# ICTester_v1.net
KiCad netlist of a schematic drawn in EAGLE
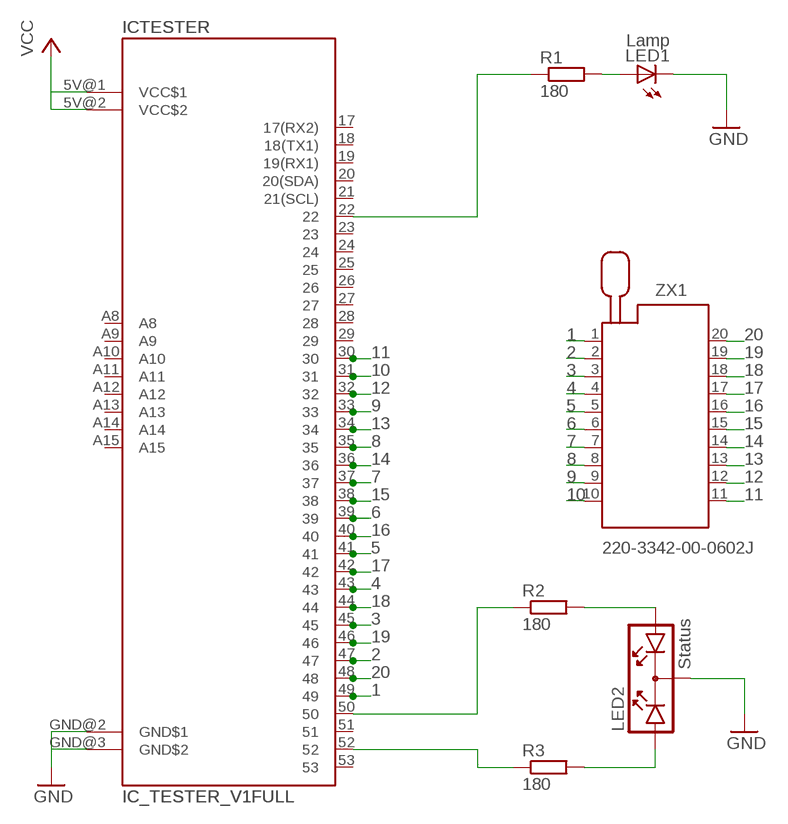
[diagram p0: schematic, sheet 1]

(export (version "E")
  (design (tool "Eeschema 10.0.6"))
  (components
    (comp (ref "ICTESTER")
      (value "IC_TESTER_V1FULL")
      (footprint "eagle-import:SPARKFUN-BOARDS_ARDUINO_MEGA")
      (libsource (lib "eagle-import") (part "IC_TESTER_V1FULL"))
    )
    (comp (ref "LED1")
      (value "Lamp")
      (footprint "eagle-import:LED3MM")
      (libsource (lib "eagle-import") (part "LED3MM"))
    )
    (comp (ref "LED2")
      (value "Status")
      (footprint "eagle-import:DUOLED")
      (libsource (lib "eagle-import") (part "DUOLED"))
    )
    (comp (ref "R1")
      (value "180")
      (footprint "eagle-import:0204V")
      (libsource (lib "eagle-import") (part "R-EU_0204/2V"))
    )
    (comp (ref "R2")
      (value "180")
      (footprint "eagle-import:0204_7")
      (libsource (lib "eagle-import") (part "R-EU_0204/7"))
    )
    (comp (ref "R3")
      (value "180")
      (footprint "eagle-import:0204_7")
      (libsource (lib "eagle-import") (part "R-EU_0204/7"))
    )
    (comp (ref "ZX1")
      (value "220-3342-00-0602J")
      (footprint "eagle-import:220-3342-00-0602J")
      (fields (field (name "MF") "3M"))
      (libsource (lib "eagle-import") (part "220-3342-00-0602J"))
    )
  )
  (nets
    (net (code "1") (name "/1") (class "Default")
      (node (ref "ICTESTER") (pin "49") (pinfunction "49_49") (pintype "bidirectional"))
      (node (ref "ZX1") (pin "1") (pinfunction "1_1") (pintype "passive"))
    )
    (net (code "2") (name "/2") (class "Default")
      (node (ref "ICTESTER") (pin "47") (pinfunction "47_47") (pintype "bidirectional"))
      (node (ref "ZX1") (pin "2") (pinfunction "2_2") (pintype "passive"))
    )
    (net (code "3") (name "/3") (class "Default")
      (node (ref "ICTESTER") (pin "45") (pinfunction "45_45") (pintype "bidirectional"))
      (node (ref "ZX1") (pin "3") (pinfunction "3_3") (pintype "passive"))
    )
    (net (code "4") (name "/4") (class "Default")
      (node (ref "ICTESTER") (pin "43") (pinfunction "43_43") (pintype "bidirectional"))
      (node (ref "ZX1") (pin "4") (pinfunction "4_4") (pintype "passive"))
    )
    (net (code "5") (name "/5") (class "Default")
      (node (ref "ICTESTER") (pin "41") (pinfunction "41_41") (pintype "bidirectional"))
      (node (ref "ZX1") (pin "5") (pinfunction "5_5") (pintype "passive"))
    )
    (net (code "6") (name "/6") (class "Default")
      (node (ref "ICTESTER") (pin "39") (pinfunction "39_39") (pintype "bidirectional"))
      (node (ref "ZX1") (pin "6") (pinfunction "6_6") (pintype "passive"))
    )
    (net (code "7") (name "/7") (class "Default")
      (node (ref "ICTESTER") (pin "37") (pinfunction "37_37") (pintype "bidirectional"))
      (node (ref "ZX1") (pin "7") (pinfunction "7_7") (pintype "passive"))
    )
    (net (code "8") (name "/8") (class "Default")
      (node (ref "ICTESTER") (pin "35") (pinfunction "35_35") (pintype "bidirectional"))
      (node (ref "ZX1") (pin "8") (pinfunction "8_8") (pintype "passive"))
    )
    (net (code "9") (name "/9") (class "Default")
      (node (ref "ICTESTER") (pin "33") (pinfunction "33_33") (pintype "bidirectional"))
      (node (ref "ZX1") (pin "9") (pinfunction "9_9") (pintype "passive"))
    )
    (net (code "10") (name "/10") (class "Default")
      (node (ref "ICTESTER") (pin "31") (pinfunction "31_31") (pintype "bidirectional"))
      (node (ref "ZX1") (pin "10") (pinfunction "10_10") (pintype "passive"))
    )
    (net (code "11") (name "/11") (class "Default")
      (node (ref "ICTESTER") (pin "30") (pinfunction "30_30") (pintype "bidirectional"))
      (node (ref "ZX1") (pin "11") (pinfunction "11_11") (pintype "passive"))
    )
    (net (code "12") (name "/12") (class "Default")
      (node (ref "ICTESTER") (pin "32") (pinfunction "32_32") (pintype "bidirectional"))
      (node (ref "ZX1") (pin "12") (pinfunction "12_12") (pintype "passive"))
    )
    (net (code "13") (name "/13") (class "Default")
      (node (ref "ICTESTER") (pin "34") (pinfunction "34_34") (pintype "bidirectional"))
      (node (ref "ZX1") (pin "13") (pinfunction "13_13") (pintype "passive"))
    )
    (net (code "14") (name "/14") (class "Default")
      (node (ref "ICTESTER") (pin "36") (pinfunction "36_36") (pintype "bidirectional"))
      (node (ref "ZX1") (pin "14") (pinfunction "14_14") (pintype "passive"))
    )
    (net (code "15") (name "/15") (class "Default")
      (node (ref "ICTESTER") (pin "38") (pinfunction "38_38") (pintype "bidirectional"))
      (node (ref "ZX1") (pin "15") (pinfunction "15_15") (pintype "passive"))
    )
    (net (code "16") (name "/16") (class "Default")
      (node (ref "ICTESTER") (pin "40") (pinfunction "40_40") (pintype "bidirectional"))
      (node (ref "ZX1") (pin "16") (pinfunction "16_16") (pintype "passive"))
    )
    (net (code "17") (name "/17") (class "Default")
      (node (ref "ICTESTER") (pin "42") (pinfunction "42_42") (pintype "bidirectional"))
      (node (ref "ZX1") (pin "17") (pinfunction "17_17") (pintype "passive"))
    )
    (net (code "18") (name "/18") (class "Default")
      (node (ref "ICTESTER") (pin "44") (pinfunction "44_44") (pintype "bidirectional"))
      (node (ref "ZX1") (pin "18") (pinfunction "18_18") (pintype "passive"))
    )
    (net (code "19") (name "/19") (class "Default")
      (node (ref "ICTESTER") (pin "46") (pinfunction "46_46") (pintype "bidirectional"))
      (node (ref "ZX1") (pin "19") (pinfunction "19_19") (pintype "passive"))
    )
    (net (code "20") (name "/20") (class "Default")
      (node (ref "ICTESTER") (pin "48") (pinfunction "48_48") (pintype "bidirectional"))
      (node (ref "ZX1") (pin "20") (pinfunction "20_20") (pintype "passive"))
    )
    (net (code "21") (name "GND") (class "Default")
      (node (ref "ICTESTER") (pin "GND@2") (pinfunction "GND$1_GND@2") (pintype "power_in"))
      (node (ref "ICTESTER") (pin "GND@3") (pinfunction "GND$2_GND@3") (pintype "power_in"))
      (node (ref "LED1") (pin "K") (pinfunction "C_K") (pintype "passive"))
      (node (ref "LED2") (pin "K") (pinfunction "K_K") (pintype "passive"))
    )
    (net (code "22") (name "Net-(ICTESTER-Pad22)") (class "Default")
      (node (ref "ICTESTER") (pin "22") (pinfunction "22_22") (pintype "bidirectional"))
      (node (ref "R1") (pin "1") (pinfunction "1_1") (pintype "passive"))
    )
    (net (code "23") (name "Net-(ICTESTER-Pad50)") (class "Default")
      (node (ref "ICTESTER") (pin "50") (pinfunction "50_50") (pintype "bidirectional"))
      (node (ref "R2") (pin "1") (pinfunction "1_1") (pintype "passive"))
    )
    (net (code "24") (name "Net-(ICTESTER-Pad52)") (class "Default")
      (node (ref "ICTESTER") (pin "52") (pinfunction "52_52") (pintype "bidirectional"))
      (node (ref "R3") (pin "1") (pinfunction "1_1") (pintype "passive"))
    )
    (net (code "25") (name "Net-(LED1-PadA)") (class "Default")
      (node (ref "LED1") (pin "A") (pinfunction "A_A") (pintype "passive"))
      (node (ref "R1") (pin "2") (pinfunction "2_2") (pintype "passive"))
    )
    (net (code "26") (name "Net-(LED2-PadA1)") (class "Default")
      (node (ref "LED2") (pin "A1") (pinfunction "A1_A1") (pintype "passive"))
      (node (ref "R3") (pin "2") (pinfunction "2_2") (pintype "passive"))
    )
    (net (code "27") (name "Net-(LED2-PadA2)") (class "Default")
      (node (ref "LED2") (pin "A2") (pinfunction "A2_A2") (pintype "passive"))
      (node (ref "R2") (pin "2") (pinfunction "2_2") (pintype "passive"))
    )
    (net (code "28") (name "VCC") (class "Default")
      (node (ref "ICTESTER") (pin "5V@1") (pinfunction "VCC$1_5V@1") (pintype "power_in"))
      (node (ref "ICTESTER") (pin "5V@2") (pinfunction "VCC$2_5V@2") (pintype "power_in"))
    )
    (net (code "29") (name "unconnected-(ICTESTER-17(RX2)-Pad17)") (class "Default")
      (node (ref "ICTESTER") (pin "17") (pinfunction "17(RX2)_17") (pintype "bidirectional"))
    )
    (net (code "30") (name "unconnected-(ICTESTER-18(TX1)-Pad18)") (class "Default")
      (node (ref "ICTESTER") (pin "18") (pinfunction "18(TX1)_18") (pintype "bidirectional"))
    )
    (net (code "31") (name "unconnected-(ICTESTER-19(RX1)-Pad19)") (class "Default")
      (node (ref "ICTESTER") (pin "19") (pinfunction "19(RX1)_19") (pintype "bidirectional"))
    )
    (net (code "32") (name "unconnected-(ICTESTER-20(SDA)-Pad20)") (class "Default")
      (node (ref "ICTESTER") (pin "20") (pinfunction "20(SDA)_20") (pintype "bidirectional"))
    )
    (net (code "33") (name "unconnected-(ICTESTER-21(SCL)-Pad21)") (class "Default")
      (node (ref "ICTESTER") (pin "21") (pinfunction "21(SCL)_21") (pintype "bidirectional"))
    )
    (net (code "34") (name "unconnected-(ICTESTER-Pad23)") (class "Default")
      (node (ref "ICTESTER") (pin "23") (pinfunction "23_23") (pintype "bidirectional"))
    )
    (net (code "35") (name "unconnected-(ICTESTER-Pad24)") (class "Default")
      (node (ref "ICTESTER") (pin "24") (pinfunction "24_24") (pintype "bidirectional"))
    )
    (net (code "36") (name "unconnected-(ICTESTER-Pad25)") (class "Default")
      (node (ref "ICTESTER") (pin "25") (pinfunction "25_25") (pintype "bidirectional"))
    )
    (net (code "37") (name "unconnected-(ICTESTER-Pad26)") (class "Default")
      (node (ref "ICTESTER") (pin "26") (pinfunction "26_26") (pintype "bidirectional"))
    )
    (net (code "38") (name "unconnected-(ICTESTER-Pad27)") (class "Default")
      (node (ref "ICTESTER") (pin "27") (pinfunction "27_27") (pintype "bidirectional"))
    )
    (net (code "39") (name "unconnected-(ICTESTER-Pad28)") (class "Default")
      (node (ref "ICTESTER") (pin "28") (pinfunction "28_28") (pintype "bidirectional"))
    )
    (net (code "40") (name "unconnected-(ICTESTER-Pad29)") (class "Default")
      (node (ref "ICTESTER") (pin "29") (pinfunction "29_29") (pintype "bidirectional"))
    )
    (net (code "41") (name "unconnected-(ICTESTER-Pad51)") (class "Default")
      (node (ref "ICTESTER") (pin "51") (pinfunction "51_51") (pintype "bidirectional"))
    )
    (net (code "42") (name "unconnected-(ICTESTER-Pad53)") (class "Default")
      (node (ref "ICTESTER") (pin "53") (pinfunction "53_53") (pintype "bidirectional"))
    )
    (net (code "43") (name "unconnected-(ICTESTER-PadA8)") (class "Default")
      (node (ref "ICTESTER") (pin "A8") (pinfunction "A8_A8") (pintype "bidirectional"))
    )
    (net (code "44") (name "unconnected-(ICTESTER-PadA9)") (class "Default")
      (node (ref "ICTESTER") (pin "A9") (pinfunction "A9_A9") (pintype "bidirectional"))
    )
    (net (code "45") (name "unconnected-(ICTESTER-PadA10)") (class "Default")
      (node (ref "ICTESTER") (pin "A10") (pinfunction "A10_A10") (pintype "bidirectional"))
    )
    (net (code "46") (name "unconnected-(ICTESTER-PadA11)") (class "Default")
      (node (ref "ICTESTER") (pin "A11") (pinfunction "A11_A11") (pintype "bidirectional"))
    )
    (net (code "47") (name "unconnected-(ICTESTER-PadA12)") (class "Default")
      (node (ref "ICTESTER") (pin "A12") (pinfunction "A12_A12") (pintype "bidirectional"))
    )
    (net (code "48") (name "unconnected-(ICTESTER-PadA13)") (class "Default")
      (node (ref "ICTESTER") (pin "A13") (pinfunction "A13_A13") (pintype "bidirectional"))
    )
    (net (code "49") (name "unconnected-(ICTESTER-PadA14)") (class "Default")
      (node (ref "ICTESTER") (pin "A14") (pinfunction "A14_A14") (pintype "bidirectional"))
    )
    (net (code "50") (name "unconnected-(ICTESTER-PadA15)") (class "Default")
      (node (ref "ICTESTER") (pin "A15") (pinfunction "A15_A15") (pintype "bidirectional"))
    )
  )
)
